# redBoard_r1.net
KiCad netlist of a schematic drawn in EAGLE
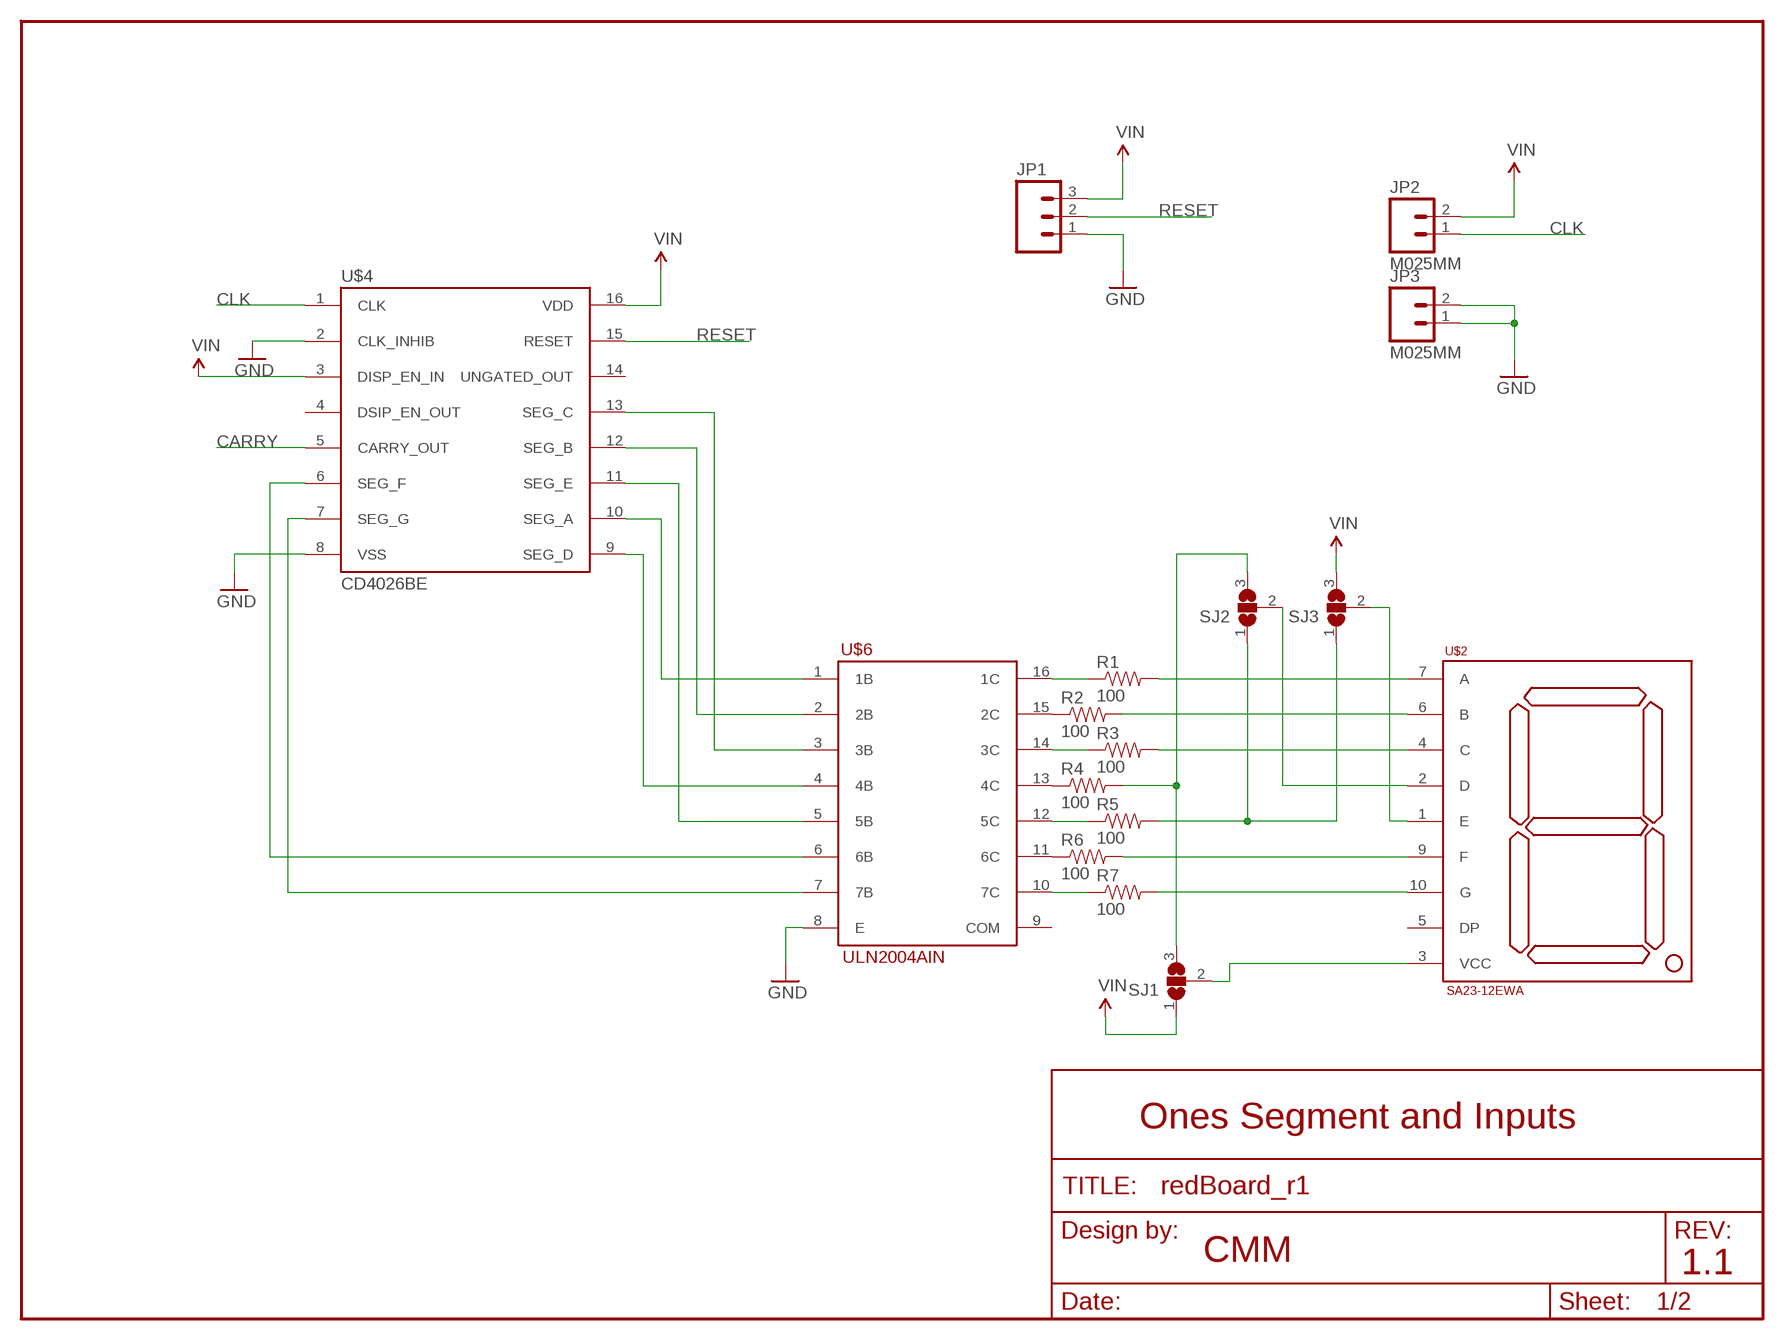
[diagram p0: schematic, sheet 1]
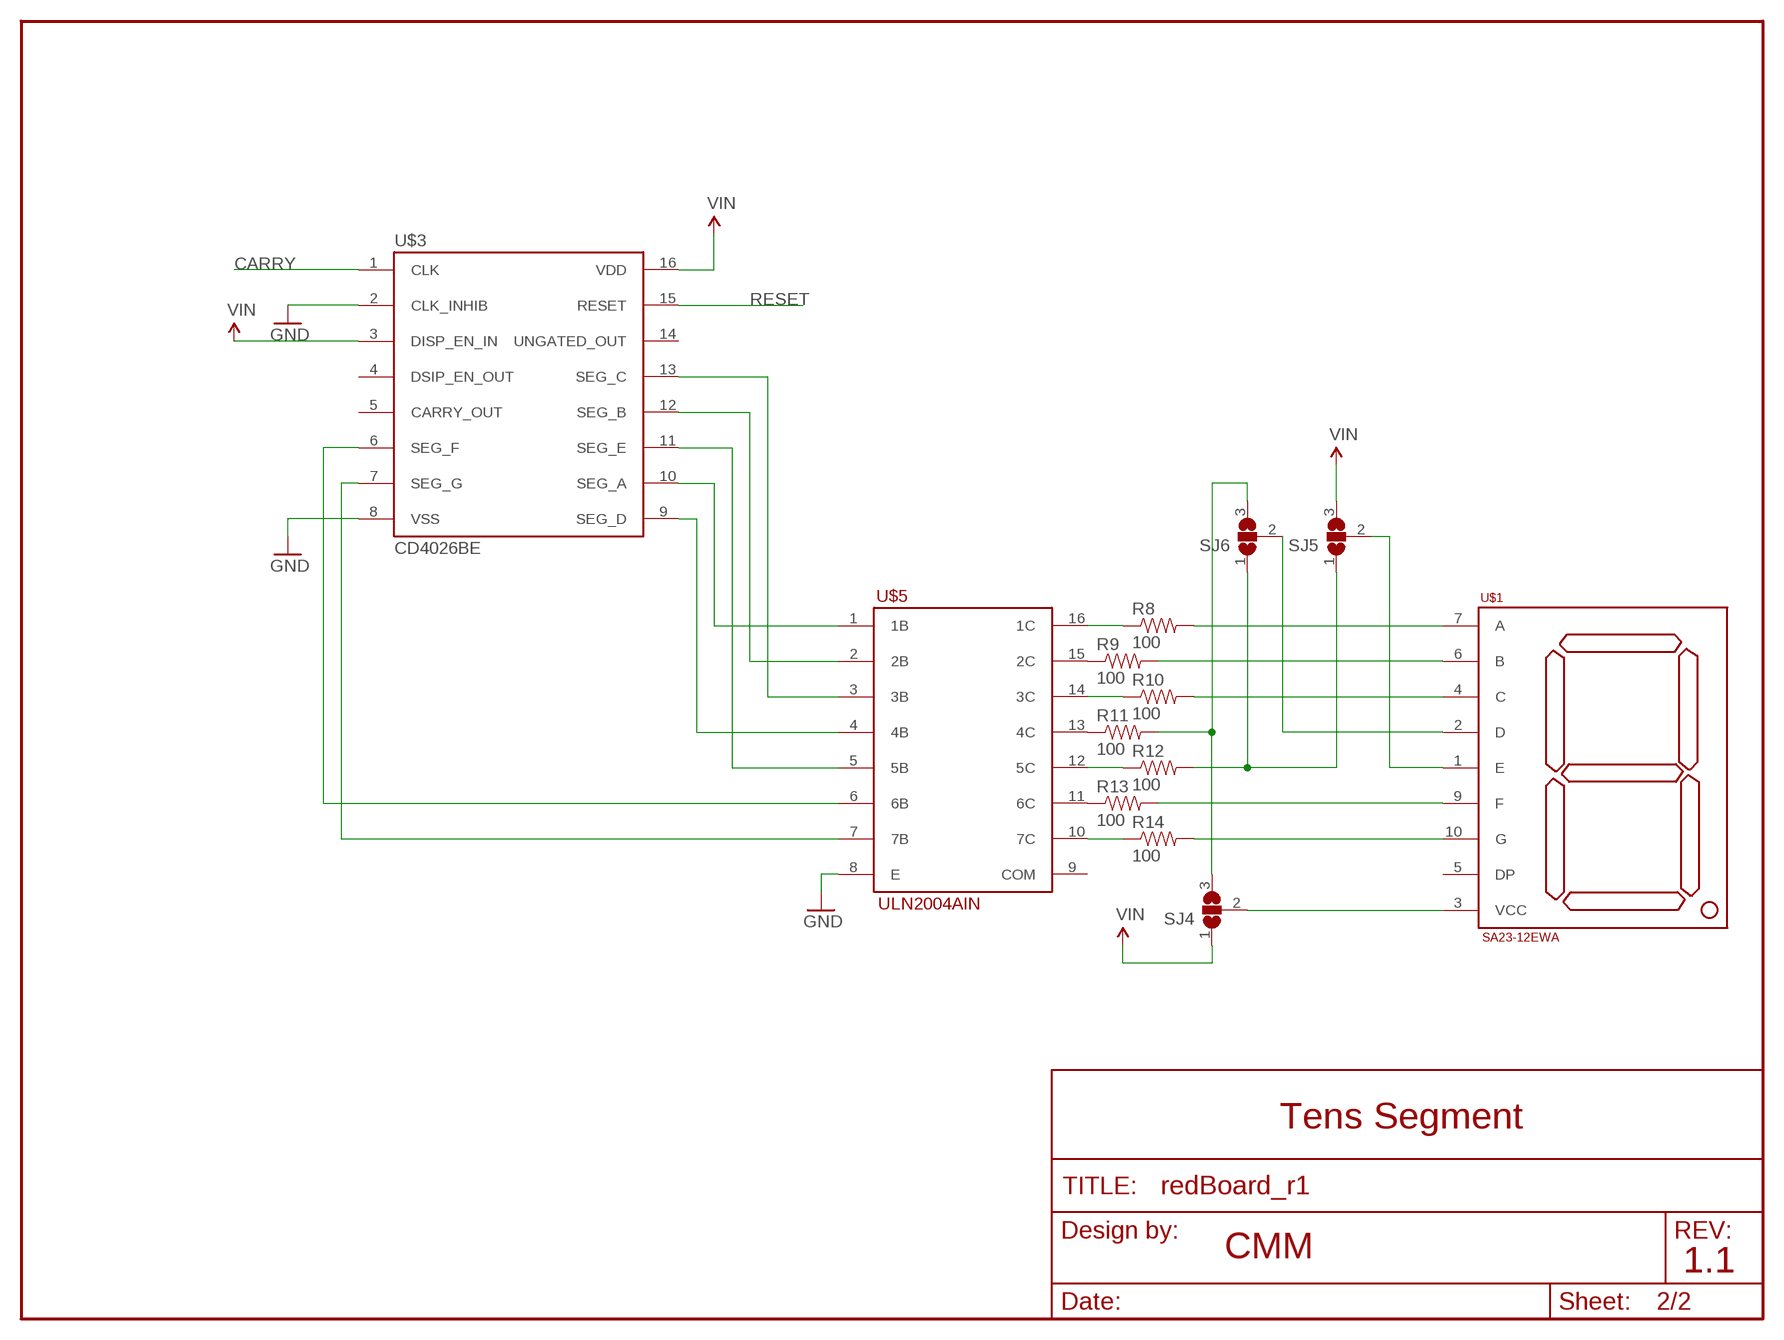
[diagram p1: schematic, sheet 2]

(export (version "E")
  (design (tool "Eeschema 10.0.6"))
  (components
    (comp (ref "FRAME2")
      (value "FRAME-LETTERNOTEXT")
      (footprint "eagle-import:BLANK")
      (libsource (lib "eagle-import") (part "FRAME-LETTERNOTEXT"))
    )
    (comp (ref "JP1")
      (value "M03-SCREW-5MM")
      (footprint "eagle-import:SCREWTERMINAL-5MM-3")
      (libsource (lib "eagle-import") (part "M03-SCREW-5MM"))
    )
    (comp (ref "JP2")
      (value "M025MM")
      (footprint "eagle-import:SCREWTERMINAL-5MM-2")
      (libsource (lib "eagle-import") (part "M025MM"))
    )
    (comp (ref "JP3")
      (value "M025MM")
      (footprint "eagle-import:SCREWTERMINAL-5MM-2")
      (libsource (lib "eagle-import") (part "M025MM"))
    )
    (comp (ref "R1")
      (value "100")
      (footprint "eagle-import:AXIAL-0.3")
      (libsource (lib "eagle-import") (part "100OHM-1/4W-1%(PTH)"))
    )
    (comp (ref "R2")
      (value "100")
      (footprint "eagle-import:AXIAL-0.3")
      (libsource (lib "eagle-import") (part "100OHM-1/4W-1%(PTH)"))
    )
    (comp (ref "R3")
      (value "100")
      (footprint "eagle-import:AXIAL-0.3")
      (libsource (lib "eagle-import") (part "100OHM-1/4W-1%(PTH)"))
    )
    (comp (ref "R4")
      (value "100")
      (footprint "eagle-import:AXIAL-0.3")
      (libsource (lib "eagle-import") (part "100OHM-1/4W-1%(PTH)"))
    )
    (comp (ref "R5")
      (value "100")
      (footprint "eagle-import:AXIAL-0.3")
      (libsource (lib "eagle-import") (part "100OHM-1/4W-1%(PTH)"))
    )
    (comp (ref "R6")
      (value "100")
      (footprint "eagle-import:AXIAL-0.3")
      (libsource (lib "eagle-import") (part "100OHM-1/4W-1%(PTH)"))
    )
    (comp (ref "R7")
      (value "100")
      (footprint "eagle-import:AXIAL-0.3")
      (libsource (lib "eagle-import") (part "100OHM-1/4W-1%(PTH)"))
    )
    (comp (ref "SJ1")
      (value "SJ2W")
      (footprint "eagle-import:SJ_2")
      (libsource (lib "eagle-import") (part "SJ2W"))
    )
    (comp (ref "SJ2")
      (value "SJ2W")
      (footprint "eagle-import:SJ_2")
      (libsource (lib "eagle-import") (part "SJ2W"))
    )
    (comp (ref "SJ3")
      (value "SJ2W")
      (footprint "eagle-import:SJ_2")
      (libsource (lib "eagle-import") (part "SJ2W"))
    )
    (comp (ref "U$2")
      (value "SA23-12EWA")
      (footprint "eagle-import:7SEGMENT_23IN")
      (libsource (lib "eagle-import") (part "SA23-12EWA"))
    )
    (comp (ref "U$4")
      (value "CD4026BE")
      (footprint "eagle-import:DIL16")
      (libsource (lib "eagle-import") (part "CD4026BE"))
    )
    (comp (ref "U$6")
      (value "ULN2004AIN")
      (footprint "eagle-import:DIL16")
      (libsource (lib "eagle-import") (part "ULN2004AIN"))
    )
    (comp (ref "FRAME1")
      (value "FRAME-LETTERNOTEXT")
      (footprint "eagle-import:BLANK")
      (libsource (lib "eagle-import") (part "FRAME-LETTERNOTEXT"))
    )
    (comp (ref "R8")
      (value "100")
      (footprint "eagle-import:AXIAL-0.3")
      (libsource (lib "eagle-import") (part "100OHM-1/4W-1%(PTH)"))
    )
    (comp (ref "R9")
      (value "100")
      (footprint "eagle-import:AXIAL-0.3")
      (libsource (lib "eagle-import") (part "100OHM-1/4W-1%(PTH)"))
    )
    (comp (ref "R10")
      (value "100")
      (footprint "eagle-import:AXIAL-0.3")
      (libsource (lib "eagle-import") (part "100OHM-1/4W-1%(PTH)"))
    )
    (comp (ref "R11")
      (value "100")
      (footprint "eagle-import:AXIAL-0.3")
      (libsource (lib "eagle-import") (part "100OHM-1/4W-1%(PTH)"))
    )
    (comp (ref "R12")
      (value "100")
      (footprint "eagle-import:AXIAL-0.3")
      (libsource (lib "eagle-import") (part "100OHM-1/4W-1%(PTH)"))
    )
    (comp (ref "R13")
      (value "100")
      (footprint "eagle-import:AXIAL-0.3")
      (libsource (lib "eagle-import") (part "100OHM-1/4W-1%(PTH)"))
    )
    (comp (ref "R14")
      (value "100")
      (footprint "eagle-import:AXIAL-0.3")
      (libsource (lib "eagle-import") (part "100OHM-1/4W-1%(PTH)"))
    )
    (comp (ref "SJ4")
      (value "SJ2W")
      (footprint "eagle-import:SJ_2")
      (libsource (lib "eagle-import") (part "SJ2W"))
    )
    (comp (ref "SJ5")
      (value "SJ2W")
      (footprint "eagle-import:SJ_2")
      (libsource (lib "eagle-import") (part "SJ2W"))
    )
    (comp (ref "SJ6")
      (value "SJ2W")
      (footprint "eagle-import:SJ_2")
      (libsource (lib "eagle-import") (part "SJ2W"))
    )
    (comp (ref "U$1")
      (value "SA23-12EWA")
      (footprint "eagle-import:7SEGMENT_23IN")
      (libsource (lib "eagle-import") (part "SA23-12EWA"))
    )
    (comp (ref "U$3")
      (value "CD4026BE")
      (footprint "eagle-import:DIL16")
      (libsource (lib "eagle-import") (part "CD4026BE"))
    )
    (comp (ref "U$5")
      (value "ULN2004AIN")
      (footprint "eagle-import:DIL16")
      (libsource (lib "eagle-import") (part "ULN2004AIN"))
    )
  )
  (nets
    (net (code "1") (name "CARRY") (class "Default")
      (node (ref "U$3") (pin "1") (pinfunction "CLK_1") (pintype "input"))
      (node (ref "U$4") (pin "5") (pinfunction "CARRY_OUT_5") (pintype "output"))
    )
    (net (code "2") (name "CLK") (class "Default")
      (node (ref "JP2") (pin "1") (pinfunction "1_1") (pintype "passive"))
      (node (ref "U$4") (pin "1") (pinfunction "CLK_1") (pintype "input"))
    )
    (net (code "3") (name "GND") (class "Default")
      (node (ref "JP1") (pin "1") (pinfunction "1_1") (pintype "passive"))
      (node (ref "JP3") (pin "1") (pinfunction "1_1") (pintype "passive"))
      (node (ref "JP3") (pin "2") (pinfunction "2_2") (pintype "passive"))
      (node (ref "U$3") (pin "2") (pinfunction "CLK_INHIB_2") (pintype "input"))
      (node (ref "U$3") (pin "8") (pinfunction "VSS_8") (pintype "power_in"))
      (node (ref "U$4") (pin "2") (pinfunction "CLK_INHIB_2") (pintype "input"))
      (node (ref "U$4") (pin "8") (pinfunction "VSS_8") (pintype "power_in"))
      (node (ref "U$5") (pin "8") (pinfunction "E_8") (pintype "bidirectional"))
      (node (ref "U$6") (pin "8") (pinfunction "E_8") (pintype "bidirectional"))
    )
    (net (code "4") (name "Net-(R1-1)") (class "Default")
      (node (ref "R1") (pin "P$1") (pinfunction "1_P$1") (pintype "passive"))
      (node (ref "U$6") (pin "16") (pinfunction "1C_16") (pintype "output"))
    )
    (net (code "5") (name "Net-(R1-2)") (class "Default")
      (node (ref "R1") (pin "P$2") (pinfunction "2_P$2") (pintype "passive"))
      (node (ref "U$2") (pin "7") (pinfunction "A_7") (pintype "bidirectional"))
    )
    (net (code "6") (name "Net-(R2-1)") (class "Default")
      (node (ref "R2") (pin "P$1") (pinfunction "1_P$1") (pintype "passive"))
      (node (ref "U$6") (pin "15") (pinfunction "2C_15") (pintype "output"))
    )
    (net (code "7") (name "Net-(R2-2)") (class "Default")
      (node (ref "R2") (pin "P$2") (pinfunction "2_P$2") (pintype "passive"))
      (node (ref "U$2") (pin "6") (pinfunction "B_6") (pintype "bidirectional"))
    )
    (net (code "8") (name "Net-(R3-1)") (class "Default")
      (node (ref "R3") (pin "P$1") (pinfunction "1_P$1") (pintype "passive"))
      (node (ref "U$6") (pin "14") (pinfunction "3C_14") (pintype "output"))
    )
    (net (code "9") (name "Net-(R3-2)") (class "Default")
      (node (ref "R3") (pin "P$2") (pinfunction "2_P$2") (pintype "passive"))
      (node (ref "U$2") (pin "4") (pinfunction "C_4") (pintype "bidirectional"))
    )
    (net (code "10") (name "Net-(R4-1)") (class "Default")
      (node (ref "R4") (pin "P$1") (pinfunction "1_P$1") (pintype "passive"))
      (node (ref "U$6") (pin "13") (pinfunction "4C_13") (pintype "output"))
    )
    (net (code "11") (name "Net-(R4-2)") (class "Default")
      (node (ref "R4") (pin "P$2") (pinfunction "2_P$2") (pintype "passive"))
      (node (ref "SJ1") (pin "3") (pinfunction "3_3") (pintype "passive"))
      (node (ref "SJ2") (pin "3") (pinfunction "3_3") (pintype "passive"))
    )
    (net (code "12") (name "Net-(R5-1)") (class "Default")
      (node (ref "R5") (pin "P$1") (pinfunction "1_P$1") (pintype "passive"))
      (node (ref "U$6") (pin "12") (pinfunction "5C_12") (pintype "output"))
    )
    (net (code "13") (name "Net-(R5-2)") (class "Default")
      (node (ref "R5") (pin "P$2") (pinfunction "2_P$2") (pintype "passive"))
      (node (ref "SJ2") (pin "1") (pinfunction "1_1") (pintype "passive"))
      (node (ref "SJ3") (pin "1") (pinfunction "1_1") (pintype "passive"))
    )
    (net (code "14") (name "Net-(R6-1)") (class "Default")
      (node (ref "R6") (pin "P$1") (pinfunction "1_P$1") (pintype "passive"))
      (node (ref "U$6") (pin "11") (pinfunction "6C_11") (pintype "output"))
    )
    (net (code "15") (name "Net-(R6-2)") (class "Default")
      (node (ref "R6") (pin "P$2") (pinfunction "2_P$2") (pintype "passive"))
      (node (ref "U$2") (pin "9") (pinfunction "F_9") (pintype "bidirectional"))
    )
    (net (code "16") (name "Net-(R7-1)") (class "Default")
      (node (ref "R7") (pin "P$1") (pinfunction "1_P$1") (pintype "passive"))
      (node (ref "U$6") (pin "10") (pinfunction "7C_10") (pintype "output"))
    )
    (net (code "17") (name "Net-(R7-2)") (class "Default")
      (node (ref "R7") (pin "P$2") (pinfunction "2_P$2") (pintype "passive"))
      (node (ref "U$2") (pin "10") (pinfunction "G_10") (pintype "bidirectional"))
    )
    (net (code "18") (name "Net-(R8-1)") (class "Default")
      (node (ref "R8") (pin "P$1") (pinfunction "1_P$1") (pintype "passive"))
      (node (ref "U$5") (pin "16") (pinfunction "1C_16") (pintype "output"))
    )
    (net (code "19") (name "Net-(R8-2)") (class "Default")
      (node (ref "R8") (pin "P$2") (pinfunction "2_P$2") (pintype "passive"))
      (node (ref "U$1") (pin "7") (pinfunction "A_7") (pintype "bidirectional"))
    )
    (net (code "20") (name "Net-(R9-1)") (class "Default")
      (node (ref "R9") (pin "P$1") (pinfunction "1_P$1") (pintype "passive"))
      (node (ref "U$5") (pin "15") (pinfunction "2C_15") (pintype "output"))
    )
    (net (code "21") (name "Net-(R9-2)") (class "Default")
      (node (ref "R9") (pin "P$2") (pinfunction "2_P$2") (pintype "passive"))
      (node (ref "U$1") (pin "6") (pinfunction "B_6") (pintype "bidirectional"))
    )
    (net (code "22") (name "Net-(R10-1)") (class "Default")
      (node (ref "R10") (pin "P$1") (pinfunction "1_P$1") (pintype "passive"))
      (node (ref "U$5") (pin "14") (pinfunction "3C_14") (pintype "output"))
    )
    (net (code "23") (name "Net-(R10-2)") (class "Default")
      (node (ref "R10") (pin "P$2") (pinfunction "2_P$2") (pintype "passive"))
      (node (ref "U$1") (pin "4") (pinfunction "C_4") (pintype "bidirectional"))
    )
    (net (code "24") (name "Net-(R11-1)") (class "Default")
      (node (ref "R11") (pin "P$1") (pinfunction "1_P$1") (pintype "passive"))
      (node (ref "U$5") (pin "13") (pinfunction "4C_13") (pintype "output"))
    )
    (net (code "25") (name "Net-(R11-2)") (class "Default")
      (node (ref "R11") (pin "P$2") (pinfunction "2_P$2") (pintype "passive"))
      (node (ref "SJ4") (pin "3") (pinfunction "3_3") (pintype "passive"))
      (node (ref "SJ6") (pin "3") (pinfunction "3_3") (pintype "passive"))
    )
    (net (code "26") (name "Net-(R12-1)") (class "Default")
      (node (ref "R12") (pin "P$1") (pinfunction "1_P$1") (pintype "passive"))
      (node (ref "U$5") (pin "12") (pinfunction "5C_12") (pintype "output"))
    )
    (net (code "27") (name "Net-(R12-2)") (class "Default")
      (node (ref "R12") (pin "P$2") (pinfunction "2_P$2") (pintype "passive"))
      (node (ref "SJ5") (pin "1") (pinfunction "1_1") (pintype "passive"))
      (node (ref "SJ6") (pin "1") (pinfunction "1_1") (pintype "passive"))
    )
    (net (code "28") (name "Net-(R13-1)") (class "Default")
      (node (ref "R13") (pin "P$1") (pinfunction "1_P$1") (pintype "passive"))
      (node (ref "U$5") (pin "11") (pinfunction "6C_11") (pintype "output"))
    )
    (net (code "29") (name "Net-(R13-2)") (class "Default")
      (node (ref "R13") (pin "P$2") (pinfunction "2_P$2") (pintype "passive"))
      (node (ref "U$1") (pin "9") (pinfunction "F_9") (pintype "bidirectional"))
    )
    (net (code "30") (name "Net-(R14-1)") (class "Default")
      (node (ref "R14") (pin "P$1") (pinfunction "1_P$1") (pintype "passive"))
      (node (ref "U$5") (pin "10") (pinfunction "7C_10") (pintype "output"))
    )
    (net (code "31") (name "Net-(R14-2)") (class "Default")
      (node (ref "R14") (pin "P$2") (pinfunction "2_P$2") (pintype "passive"))
      (node (ref "U$1") (pin "10") (pinfunction "G_10") (pintype "bidirectional"))
    )
    (net (code "32") (name "Net-(U$1-D)") (class "Default")
      (node (ref "SJ6") (pin "2") (pinfunction "2_2") (pintype "passive"))
      (node (ref "U$1") (pin "2") (pinfunction "D_2") (pintype "bidirectional"))
    )
    (net (code "33") (name "Net-(U$1-E)") (class "Default")
      (node (ref "SJ5") (pin "2") (pinfunction "2_2") (pintype "passive"))
      (node (ref "U$1") (pin "1") (pinfunction "E_1") (pintype "bidirectional"))
    )
    (net (code "34") (name "Net-(U$1-VCC)") (class "Default")
      (node (ref "SJ4") (pin "2") (pinfunction "2_2") (pintype "passive"))
      (node (ref "U$1") (pin "3") (pinfunction "VCC_3") (pintype "bidirectional"))
    )
    (net (code "35") (name "Net-(U$2-D)") (class "Default")
      (node (ref "SJ2") (pin "2") (pinfunction "2_2") (pintype "passive"))
      (node (ref "U$2") (pin "2") (pinfunction "D_2") (pintype "bidirectional"))
    )
    (net (code "36") (name "Net-(U$2-E)") (class "Default")
      (node (ref "SJ3") (pin "2") (pinfunction "2_2") (pintype "passive"))
      (node (ref "U$2") (pin "1") (pinfunction "E_1") (pintype "bidirectional"))
    )
    (net (code "37") (name "Net-(U$2-VCC)") (class "Default")
      (node (ref "SJ1") (pin "2") (pinfunction "2_2") (pintype "passive"))
      (node (ref "U$2") (pin "3") (pinfunction "VCC_3") (pintype "bidirectional"))
    )
    (net (code "38") (name "Net-(U$3-SEG_A)") (class "Default")
      (node (ref "U$3") (pin "10") (pinfunction "SEG_A_10") (pintype "output"))
      (node (ref "U$5") (pin "1") (pinfunction "1B_1") (pintype "input"))
    )
    (net (code "39") (name "Net-(U$3-SEG_B)") (class "Default")
      (node (ref "U$3") (pin "12") (pinfunction "SEG_B_12") (pintype "output"))
      (node (ref "U$5") (pin "2") (pinfunction "2B_2") (pintype "input"))
    )
    (net (code "40") (name "Net-(U$3-SEG_C)") (class "Default")
      (node (ref "U$3") (pin "13") (pinfunction "SEG_C_13") (pintype "output"))
      (node (ref "U$5") (pin "3") (pinfunction "3B_3") (pintype "input"))
    )
    (net (code "41") (name "Net-(U$3-SEG_D)") (class "Default")
      (node (ref "U$3") (pin "9") (pinfunction "SEG_D_9") (pintype "output"))
      (node (ref "U$5") (pin "4") (pinfunction "4B_4") (pintype "input"))
    )
    (net (code "42") (name "Net-(U$3-SEG_E)") (class "Default")
      (node (ref "U$3") (pin "11") (pinfunction "SEG_E_11") (pintype "output"))
      (node (ref "U$5") (pin "5") (pinfunction "5B_5") (pintype "input"))
    )
    (net (code "43") (name "Net-(U$3-SEG_F)") (class "Default")
      (node (ref "U$3") (pin "6") (pinfunction "SEG_F_6") (pintype "output"))
      (node (ref "U$5") (pin "6") (pinfunction "6B_6") (pintype "input"))
    )
    (net (code "44") (name "Net-(U$3-SEG_G)") (class "Default")
      (node (ref "U$3") (pin "7") (pinfunction "SEG_G_7") (pintype "output"))
      (node (ref "U$5") (pin "7") (pinfunction "7B_7") (pintype "input"))
    )
    (net (code "45") (name "Net-(U$4-SEG_A)") (class "Default")
      (node (ref "U$4") (pin "10") (pinfunction "SEG_A_10") (pintype "output"))
      (node (ref "U$6") (pin "1") (pinfunction "1B_1") (pintype "input"))
    )
    (net (code "46") (name "Net-(U$4-SEG_B)") (class "Default")
      (node (ref "U$4") (pin "12") (pinfunction "SEG_B_12") (pintype "output"))
      (node (ref "U$6") (pin "2") (pinfunction "2B_2") (pintype "input"))
    )
    (net (code "47") (name "Net-(U$4-SEG_C)") (class "Default")
      (node (ref "U$4") (pin "13") (pinfunction "SEG_C_13") (pintype "output"))
      (node (ref "U$6") (pin "3") (pinfunction "3B_3") (pintype "input"))
    )
    (net (code "48") (name "Net-(U$4-SEG_D)") (class "Default")
      (node (ref "U$4") (pin "9") (pinfunction "SEG_D_9") (pintype "output"))
      (node (ref "U$6") (pin "4") (pinfunction "4B_4") (pintype "input"))
    )
    (net (code "49") (name "Net-(U$4-SEG_E)") (class "Default")
      (node (ref "U$4") (pin "11") (pinfunction "SEG_E_11") (pintype "output"))
      (node (ref "U$6") (pin "5") (pinfunction "5B_5") (pintype "input"))
    )
    (net (code "50") (name "Net-(U$4-SEG_F)") (class "Default")
      (node (ref "U$4") (pin "6") (pinfunction "SEG_F_6") (pintype "output"))
      (node (ref "U$6") (pin "6") (pinfunction "6B_6") (pintype "input"))
    )
    (net (code "51") (name "Net-(U$4-SEG_G)") (class "Default")
      (node (ref "U$4") (pin "7") (pinfunction "SEG_G_7") (pintype "output"))
      (node (ref "U$6") (pin "7") (pinfunction "7B_7") (pintype "input"))
    )
    (net (code "52") (name "RESET") (class "Default")
      (node (ref "JP1") (pin "2") (pinfunction "2_2") (pintype "passive"))
      (node (ref "U$3") (pin "15") (pinfunction "RESET_15") (pintype "input"))
      (node (ref "U$4") (pin "15") (pinfunction "RESET_15") (pintype "input"))
    )
    (net (code "53") (name "VIN") (class "Default")
      (node (ref "JP1") (pin "3") (pinfunction "3_3") (pintype "passive"))
      (node (ref "JP2") (pin "2") (pinfunction "2_2") (pintype "passive"))
      (node (ref "SJ1") (pin "1") (pinfunction "1_1") (pintype "passive"))
      (node (ref "SJ3") (pin "3") (pinfunction "3_3") (pintype "passive"))
      (node (ref "SJ4") (pin "1") (pinfunction "1_1") (pintype "passive"))
      (node (ref "SJ5") (pin "3") (pinfunction "3_3") (pintype "passive"))
      (node (ref "U$3") (pin "16") (pinfunction "VDD_16") (pintype "power_in"))
      (node (ref "U$3") (pin "3") (pinfunction "DISP_EN_IN_3") (pintype "input"))
      (node (ref "U$4") (pin "16") (pinfunction "VDD_16") (pintype "power_in"))
      (node (ref "U$4") (pin "3") (pinfunction "DISP_EN_IN_3") (pintype "input"))
    )
    (net (code "54") (name "unconnected-(U$1-DP-Pad5)") (class "Default")
      (node (ref "U$1") (pin "5") (pinfunction "DP_5") (pintype "bidirectional"))
    )
    (net (code "55") (name "unconnected-(U$2-DP-Pad5)") (class "Default")
      (node (ref "U$2") (pin "5") (pinfunction "DP_5") (pintype "bidirectional"))
    )
    (net (code "56") (name "unconnected-(U$3-CARRY_OUT-Pad5)") (class "Default")
      (node (ref "U$3") (pin "5") (pinfunction "CARRY_OUT_5") (pintype "output"))
    )
    (net (code "57") (name "unconnected-(U$3-DSIP_EN_OUT-Pad4)") (class "Default")
      (node (ref "U$3") (pin "4") (pinfunction "DSIP_EN_OUT_4") (pintype "output"))
    )
    (net (code "58") (name "unconnected-(U$3-UNGATED_OUT-Pad14)") (class "Default")
      (node (ref "U$3") (pin "14") (pinfunction "UNGATED_OUT_14") (pintype "output"))
    )
    (net (code "59") (name "unconnected-(U$4-DSIP_EN_OUT-Pad4)") (class "Default")
      (node (ref "U$4") (pin "4") (pinfunction "DSIP_EN_OUT_4") (pintype "output"))
    )
    (net (code "60") (name "unconnected-(U$4-UNGATED_OUT-Pad14)") (class "Default")
      (node (ref "U$4") (pin "14") (pinfunction "UNGATED_OUT_14") (pintype "output"))
    )
    (net (code "61") (name "unconnected-(U$5-COM-Pad9)") (class "Default")
      (node (ref "U$5") (pin "9") (pinfunction "COM_9") (pintype "bidirectional"))
    )
    (net (code "62") (name "unconnected-(U$6-COM-Pad9)") (class "Default")
      (node (ref "U$6") (pin "9") (pinfunction "COM_9") (pintype "bidirectional"))
    )
  )
)
